# Endstop_Channel.net
KiCad netlist of a schematic drawn in Altium Designer
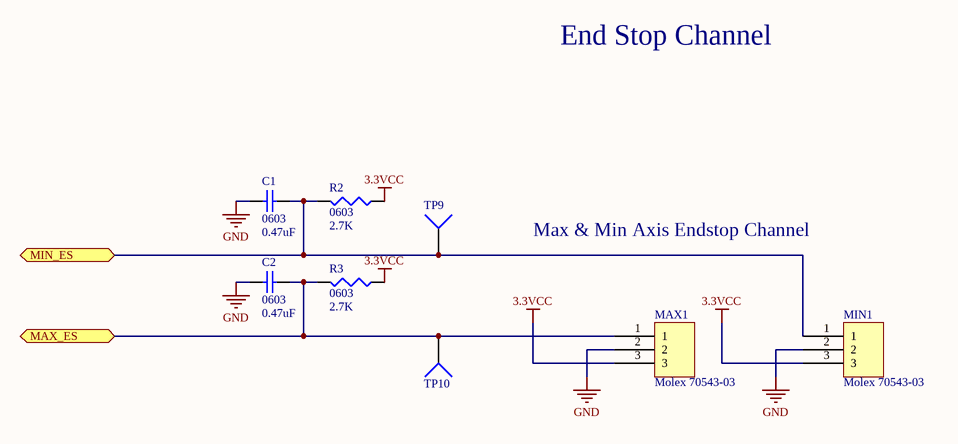
[diagram p0: Endstop Channel.SchDoc]

(export (version "E")
  (design (tool "Eeschema 10.0.6"))
  (components
    (comp (ref "C1")
      (value "0603")
      (footprint "1608[0603]")
      (description "Capacitor (Semiconductor SIM Model)")
      (fields (field (name "ALTIUM_VALUE") "0.47uF") (field (name "PUBLISHER") "Altium Limited"))
      (libsource (lib "Miscellaneous Devices") (part "Cap Semi"))
    )
    (comp (ref "C2")
      (value "0603")
      (footprint "1608[0603]")
      (description "Capacitor (Semiconductor SIM Model)")
      (fields (field (name "ALTIUM_VALUE") "0.47uF") (field (name "PUBLISHER") "Altium Limited"))
      (libsource (lib "Miscellaneous Devices") (part "Cap Semi"))
    )
    (comp (ref "MAX1")
      (value "Molex 70543-03")
      (footprint "70543-03")
      (libsource (lib "RADMBo Schematic Library") (part "Molex Endstop"))
    )
    (comp (ref "MIN1")
      (value "Molex 70543-03")
      (footprint "70543-03")
      (libsource (lib "RADMBo Schematic Library") (part "Molex Endstop"))
    )
    (comp (ref "R2")
      (value "0603")
      (footprint "J1-0603")
      (description "Resistor")
      (fields (field (name "ALTIUM_VALUE") "2.7K") (field (name "PUBLISHER") "Altium Limited"))
      (libsource (lib "Miscellaneous Devices") (part "Res3"))
    )
    (comp (ref "R3")
      (value "0603")
      (footprint "J1-0603")
      (description "Resistor")
      (fields (field (name "ALTIUM_VALUE") "2.7K") (field (name "PUBLISHER") "Altium Limited"))
      (libsource (lib "Miscellaneous Devices") (part "Res3"))
    )
    (comp (ref "TP9")
      (value "TP4")
      (footprint "TP-2")
      (description "Socket")
      (fields (field (name "PUBLISHER") "Altium Limited"))
      (libsource (lib "ZMBo Schematic Library") (part "Socket"))
    )
    (comp (ref "TP10")
      (value "TP4")
      (footprint "TP-2")
      (description "Socket")
      (fields (field (name "PUBLISHER") "Altium Limited"))
      (libsource (lib "ZMBo Schematic Library") (part "Socket"))
    )
  )
  (nets
    (net (code "1") (name "/MAX_ES") (class "Default")
      (node (ref "C2") (pin "1") (pinfunction "1_1") (pintype "passive"))
      (node (ref "MAX1") (pin "1") (pinfunction "1_1") (pintype "passive"))
      (node (ref "R3") (pin "2") (pinfunction "2_2") (pintype "passive"))
      (node (ref "TP10") (pin "1") (pinfunction "1_1") (pintype "passive"))
    )
    (net (code "2") (name "/MIN_ES") (class "Default")
      (node (ref "C1") (pin "1") (pinfunction "1_1") (pintype "passive"))
      (node (ref "MIN1") (pin "1") (pinfunction "1_1") (pintype "passive"))
      (node (ref "R2") (pin "2") (pinfunction "2_2") (pintype "passive"))
      (node (ref "TP9") (pin "1") (pinfunction "1_1") (pintype "passive"))
    )
    (net (code "3") (name "3.3VCC") (class "Default")
      (node (ref "MAX1") (pin "3") (pinfunction "3_3") (pintype "passive"))
      (node (ref "MIN1") (pin "3") (pinfunction "3_3") (pintype "passive"))
      (node (ref "R2") (pin "1") (pinfunction "1_1") (pintype "passive"))
      (node (ref "R3") (pin "1") (pinfunction "1_1") (pintype "passive"))
    )
    (net (code "4") (name "GND") (class "Default")
      (node (ref "C1") (pin "2") (pinfunction "2_2") (pintype "passive"))
      (node (ref "C2") (pin "2") (pinfunction "2_2") (pintype "passive"))
      (node (ref "MAX1") (pin "2") (pinfunction "2_2") (pintype "passive"))
      (node (ref "MIN1") (pin "2") (pinfunction "2_2") (pintype "passive"))
    )
  )
)
